# SCH_Paper-Rex-Mindset_2025-10-19.net
KiCad netlist of a schematic drawn in EasyEDA
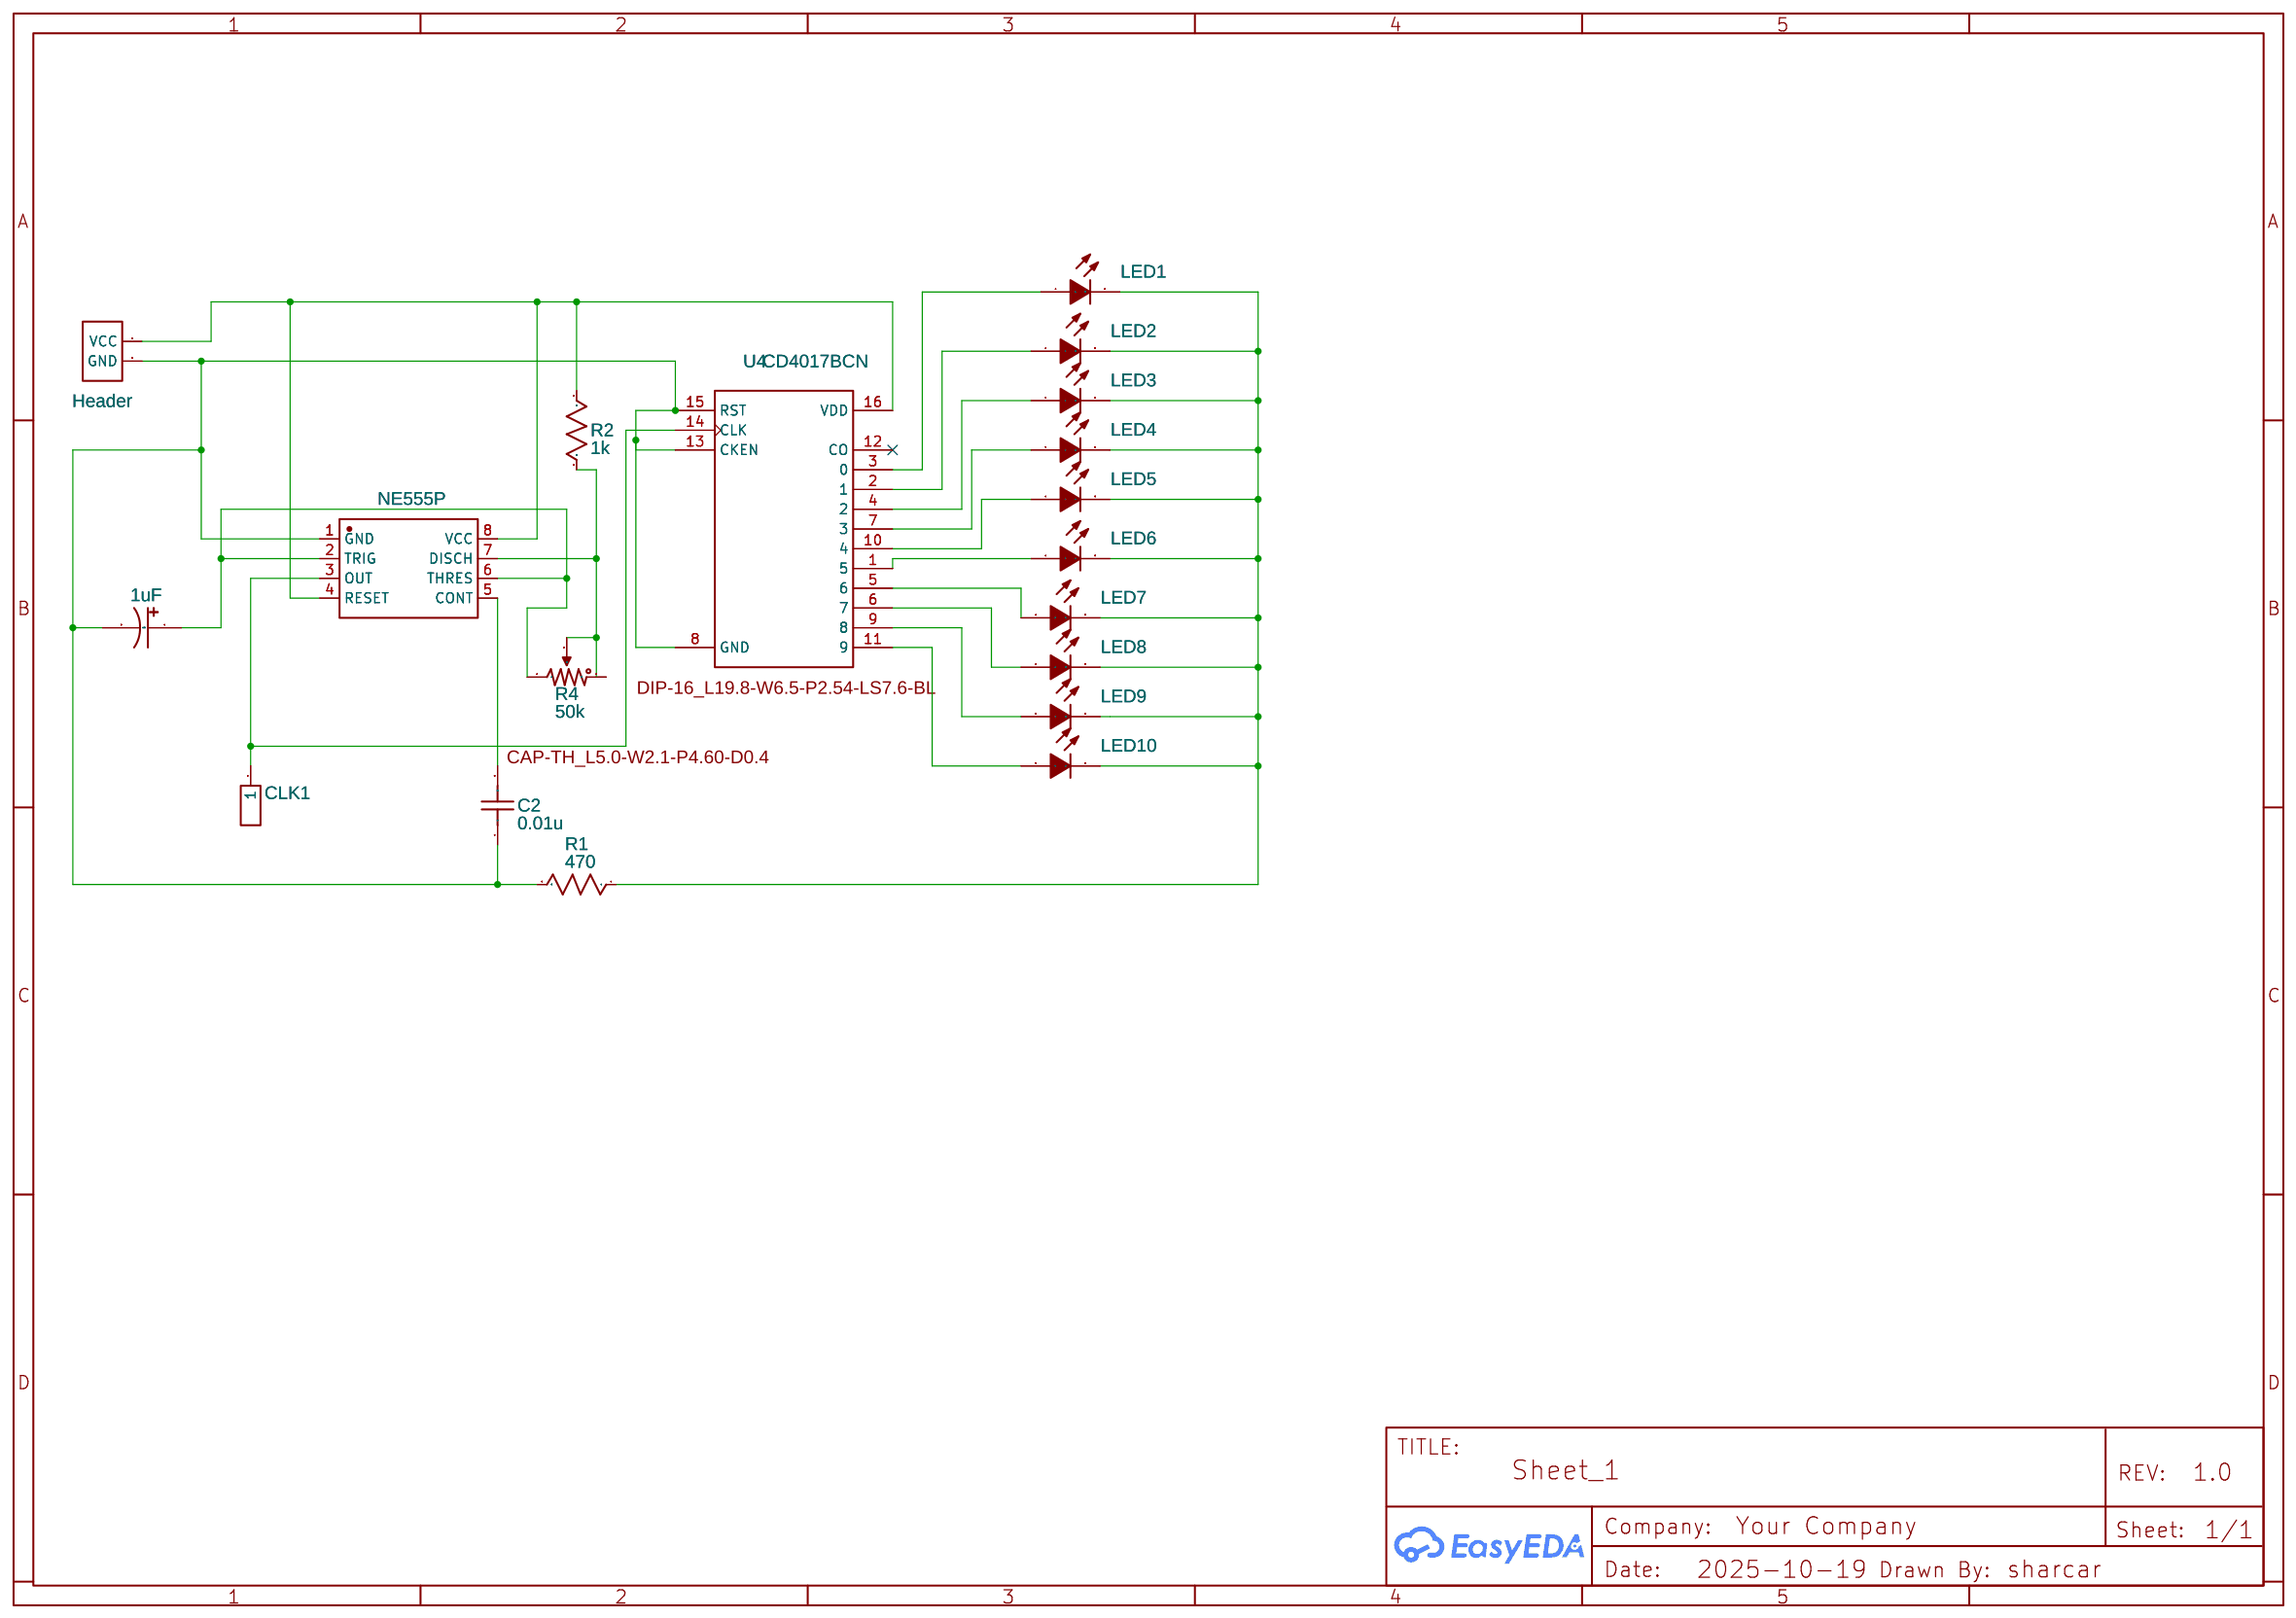
[diagram p0: schematic sheet]

(export (version "E")
  (design (tool "Eeschema 10.0.6"))
  (components
    (comp (ref "C1")
      (value "1uF")
      (fields (field (name "Manufacturer Part") "UVZ1H010MDD") (field (name "Manufacturer") "Nichicon(尼吉康)"))
      (libsource (lib "") (part "UVZ1H010MDD"))
    )
    (comp (ref "C2") (value "0.01u") (libsource (lib "") (part "C_0603_US")))
    (comp (ref "CLK1")
      (value "C81276")
      (fields
        (field (name "Manufacturer Part") "2.54-1*1P针")
        (field (name "Manufacturer") "BOOMELE(Boom Precision Elec)")
      )
      (libsource (lib "") (part "Header-Male-2.54_1x1"))
    )
    (comp (ref "H1") (value "Header") (libsource (lib "") (part "HEADER-FEMALE-2.54_1X2")))
    (comp (ref "LED1") (value "LED_5MM") (libsource (lib "") (part "LED_5MM")))
    (comp (ref "LED2") (value "LED_5MM") (libsource (lib "") (part "LED_5MM")))
    (comp (ref "LED3") (value "LED_5MM") (libsource (lib "") (part "LED_5MM")))
    (comp (ref "LED4") (value "LED_5MM") (libsource (lib "") (part "LED_5MM")))
    (comp (ref "LED5") (value "LED_5MM") (libsource (lib "") (part "LED_5MM")))
    (comp (ref "LED6") (value "LED_5MM") (libsource (lib "") (part "LED_5MM")))
    (comp (ref "LED7") (value "LED_5MM") (libsource (lib "") (part "LED_5MM")))
    (comp (ref "LED8") (value "LED_5MM") (libsource (lib "") (part "LED_5MM")))
    (comp (ref "LED9") (value "LED_5MM") (libsource (lib "") (part "LED_5MM")))
    (comp (ref "LED10") (value "LED_5MM") (libsource (lib "") (part "LED_5MM")))
    (comp (ref "R1")
      (value "470")
      (fields (field (name "Manufacturer Part") "?"))
      (libsource (lib "") (part "Resistor"))
    )
    (comp (ref "R2")
      (value "1k")
      (fields (field (name "Manufacturer Part") "?"))
      (libsource (lib "") (part "Resistor_1"))
    )
    (comp (ref "R4")
      (value "50k")
      (fields (field (name "Manufacturer Part") "?"))
      (libsource (lib "") (part "Potentiometer"))
    )
    (comp (ref "U2")
      (value "NE555P")
      (fields (field (name "Manufacturer") "TI(德州仪器)"))
      (libsource (lib "") (part "NE555P"))
    )
    (comp (ref "U4") (value "CD4017BCN") (libsource (lib "") (part "CD4017BCN")))
  )
  (nets
    (net (code "1") (name "Net-(H1-GND)") (class "Default")
      (node (ref "C1") (pin "2") (pinfunction "2_2") (pintype "unspecified"))
      (node (ref "C2") (pin "1") (pinfunction "1_1") (pintype "unspecified"))
      (node (ref "H1") (pin "2") (pinfunction "GND_2") (pintype "unspecified"))
      (node (ref "R1") (pin "2") (pinfunction "2_2") (pintype "unspecified"))
      (node (ref "U2") (pin "1") (pinfunction "GND_1") (pintype "unspecified"))
      (node (ref "U4") (pin "13") (pinfunction "CKEN_13") (pintype "unspecified"))
      (node (ref "U4") (pin "15") (pinfunction "RST_15") (pintype "unspecified"))
      (node (ref "U4") (pin "8") (pinfunction "GND_8") (pintype "passive"))
    )
    (net (code "2") (name "Net-(H1-VCC)") (class "Default")
      (node (ref "H1") (pin "1") (pinfunction "VCC_1") (pintype "unspecified"))
      (node (ref "R2") (pin "1") (pinfunction "1_1") (pintype "unspecified"))
      (node (ref "U2") (pin "4") (pinfunction "RESET_4") (pintype "unspecified"))
      (node (ref "U2") (pin "8") (pinfunction "VCC_8") (pintype "unspecified"))
      (node (ref "U4") (pin "16") (pinfunction "VDD_16") (pintype "passive"))
    )
    (net (code "3") (name "Net-(LED1-A)") (class "Default")
      (node (ref "LED1") (pin "1") (pinfunction "A_1") (pintype "input"))
      (node (ref "U4") (pin "3") (pinfunction "0_3") (pintype "output"))
    )
    (net (code "4") (name "Net-(LED1-K)") (class "Default")
      (node (ref "LED1") (pin "2") (pinfunction "K_2") (pintype "input"))
      (node (ref "LED10") (pin "2") (pinfunction "K_2") (pintype "input"))
      (node (ref "LED2") (pin "2") (pinfunction "K_2") (pintype "input"))
      (node (ref "LED3") (pin "2") (pinfunction "K_2") (pintype "input"))
      (node (ref "LED4") (pin "2") (pinfunction "K_2") (pintype "input"))
      (node (ref "LED5") (pin "2") (pinfunction "K_2") (pintype "input"))
      (node (ref "LED6") (pin "2") (pinfunction "K_2") (pintype "input"))
      (node (ref "LED7") (pin "2") (pinfunction "K_2") (pintype "input"))
      (node (ref "LED8") (pin "2") (pinfunction "K_2") (pintype "input"))
      (node (ref "LED9") (pin "2") (pinfunction "K_2") (pintype "input"))
      (node (ref "R1") (pin "1") (pinfunction "1_1") (pintype "unspecified"))
    )
    (net (code "5") (name "Net-(LED2-A)") (class "Default")
      (node (ref "LED2") (pin "1") (pinfunction "A_1") (pintype "input"))
      (node (ref "U4") (pin "2") (pinfunction "1_2") (pintype "output"))
    )
    (net (code "6") (name "Net-(LED3-A)") (class "Default")
      (node (ref "LED3") (pin "1") (pinfunction "A_1") (pintype "input"))
      (node (ref "U4") (pin "4") (pinfunction "2_4") (pintype "output"))
    )
    (net (code "7") (name "Net-(LED4-A)") (class "Default")
      (node (ref "LED4") (pin "1") (pinfunction "A_1") (pintype "input"))
      (node (ref "U4") (pin "7") (pinfunction "3_7") (pintype "output"))
    )
    (net (code "8") (name "Net-(LED5-A)") (class "Default")
      (node (ref "LED5") (pin "1") (pinfunction "A_1") (pintype "input"))
      (node (ref "U4") (pin "10") (pinfunction "4_10") (pintype "output"))
    )
    (net (code "9") (name "Net-(LED6-A)") (class "Default")
      (node (ref "LED6") (pin "1") (pinfunction "A_1") (pintype "input"))
      (node (ref "U4") (pin "1") (pinfunction "5_1") (pintype "output"))
    )
    (net (code "10") (name "Net-(LED7-A)") (class "Default")
      (node (ref "LED7") (pin "1") (pinfunction "A_1") (pintype "input"))
      (node (ref "U4") (pin "5") (pinfunction "6_5") (pintype "output"))
    )
    (net (code "11") (name "Net-(LED8-A)") (class "Default")
      (node (ref "LED8") (pin "1") (pinfunction "A_1") (pintype "input"))
      (node (ref "U4") (pin "6") (pinfunction "7_6") (pintype "output"))
    )
    (net (code "12") (name "Net-(LED9-A)") (class "Default")
      (node (ref "LED9") (pin "1") (pinfunction "A_1") (pintype "input"))
      (node (ref "U4") (pin "9") (pinfunction "8_9") (pintype "output"))
    )
    (net (code "13") (name "Net-(LED10-A)") (class "Default")
      (node (ref "LED10") (pin "1") (pinfunction "A_1") (pintype "input"))
      (node (ref "U4") (pin "11") (pinfunction "9_11") (pintype "output"))
    )
    (net (code "14") (name "Net-(R4-2)") (class "Default")
      (node (ref "R2") (pin "2") (pinfunction "2_2") (pintype "unspecified"))
      (node (ref "R4") (pin "2") (pinfunction "3_2") (pintype "unspecified"))
      (node (ref "R4") (pin "3") (pinfunction "2_3") (pintype "unspecified"))
      (node (ref "U2") (pin "7") (pinfunction "DISCH_7") (pintype "unspecified"))
    )
    (net (code "15") (name "Net-(U2-CONT)") (class "Default")
      (node (ref "C2") (pin "2") (pinfunction "2_2") (pintype "unspecified"))
      (node (ref "U2") (pin "5") (pinfunction "CONT_5") (pintype "unspecified"))
    )
    (net (code "16") (name "Net-(U2-OUT)") (class "Default")
      (node (ref "CLK1") (pin "1") (pinfunction "1_1") (pintype "unspecified"))
      (node (ref "U2") (pin "3") (pinfunction "OUT_3") (pintype "unspecified"))
      (node (ref "U4") (pin "14") (pinfunction "CLK_14") (pintype "unspecified"))
    )
    (net (code "17") (name "Net-(U2-THRES)") (class "Default")
      (node (ref "C1") (pin "1") (pinfunction "1_1") (pintype "unspecified"))
      (node (ref "R4") (pin "1") (pinfunction "1_1") (pintype "unspecified"))
      (node (ref "U2") (pin "2") (pinfunction "TRIG_2") (pintype "unspecified"))
      (node (ref "U2") (pin "6") (pinfunction "THRES_6") (pintype "unspecified"))
    )
    (net (code "18") (name "unconnected-(U4-CO-Pad12)") (class "Default")
      (node (ref "U4") (pin "12") (pinfunction "CO_12") (pintype "output+no_connect"))
    )
  )
)
